# GY_NEO6MV2_Sheet1.net
KiCad netlist of a schematic drawn in Altium Designer
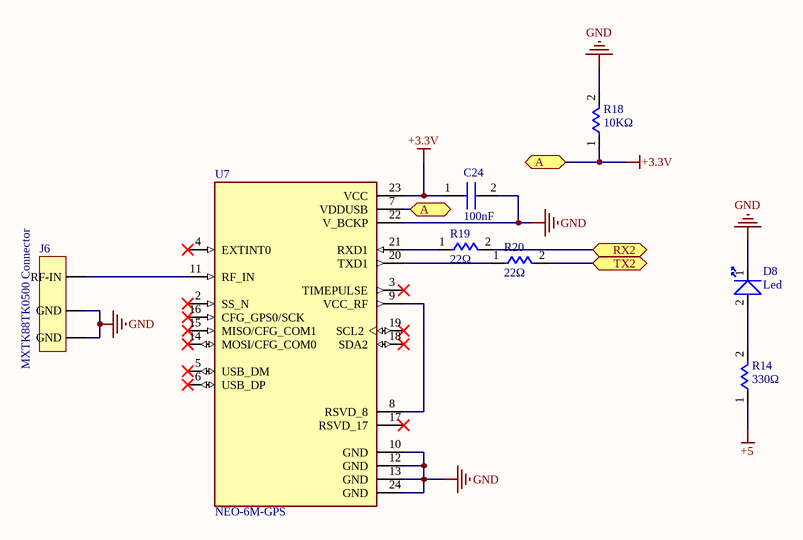
[diagram p0: GY_NEO6MV2_Sheet1.SchDoc]

(export (version "E")
  (design (tool "Eeschema 10.0.6"))
  (components
    (comp (ref "C24")
      (value "100nF")
      (footprint "CAP - 0603")
      (description "Capacitor")
      (libsource (lib "Faydali_Yuk_Schlib1") (part "CAP"))
    )
    (comp (ref "D8")
      (value "Led")
      (footprint "LED - 0603")
      (description "HL-PST-1608U51GC - LED SMD 0603 GREEN 500mcd 120° WATER CLEAR")
      (libsource (lib "Faydali_Yuk_Schlib1") (part "Led"))
    )
    (comp (ref "J6")
      (value "MXTK88TK0500 Connector")
      (footprint "MXTK88TK0500 Connector")
      (description "CABLE ASSEMBLY COAXIAL 0.5m GSC CONN.PL-PL")
      (libsource (lib "Faydali_Yuk_Schlib1") (part "MXTK88TK0500 Connector"))
    )
    (comp (ref "R14")
      (value "330Ω")
      (footprint "RES - 0603")
      (description "SMD Res")
      (libsource (lib "Faydali_Yuk_Schlib1") (part "Res"))
    )
    (comp (ref "R18")
      (value "10KΩ")
      (footprint "RES - 0603")
      (description "SMD Res")
      (libsource (lib "Faydali_Yuk_Schlib1") (part "Res"))
    )
    (comp (ref "R19")
      (value "22Ω")
      (footprint "RES - 0603")
      (description "SMD Res")
      (libsource (lib "Faydali_Yuk_Schlib1") (part "Res"))
    )
    (comp (ref "R20")
      (value "22Ω")
      (footprint "RES - 0603")
      (description "SMD Res")
      (libsource (lib "Faydali_Yuk_Schlib1") (part "Res"))
    )
    (comp (ref "U7")
      (value "NEO-6M-GPS")
      (footprint "XCVR_NEO-6M-GPS")
      (description "SMD GPS Module;")
      (fields (field (name "MF") "u-blox"))
      (libsource (lib "Faydali_Yuk_Schlib1") (part "NEO-6M-GPS"))
    )
  )
  (nets
    (net (code "1") (name "+3.3V") (class "Default")
      (node (ref "C24") (pin "1") (pinfunction "1_1") (pintype "passive"))
      (node (ref "R18") (pin "1") (pinfunction "1_1") (pintype "passive"))
      (node (ref "U7") (pin "23") (pinfunction "VCC_23") (pintype "power_in"))
      (node (ref "U7") (pin "7") (pinfunction "VDDUSB_7") (pintype "power_in"))
    )
    (net (code "2") (name "+5") (class "Default")
      (node (ref "R14") (pin "1") (pinfunction "1_1") (pintype "passive"))
    )
    (net (code "3") (name "/RX2") (class "Default")
      (node (ref "R19") (pin "2") (pinfunction "2_2") (pintype "passive"))
    )
    (net (code "4") (name "/TX2") (class "Default")
      (node (ref "R20") (pin "2") (pinfunction "2_2") (pintype "passive"))
    )
    (net (code "5") (name "GND") (class "Default")
      (node (ref "C24") (pin "2") (pinfunction "2_2") (pintype "passive"))
      (node (ref "D8") (pin "1") (pinfunction "1_1") (pintype "passive"))
      (node (ref "J6") (pin "1") (pinfunction "GND_1") (pintype "passive"))
      (node (ref "J6") (pin "2") (pinfunction "GND_2") (pintype "passive"))
      (node (ref "R18") (pin "2") (pinfunction "2_2") (pintype "passive"))
      (node (ref "U7") (pin "10") (pinfunction "GND_10") (pintype "power_in"))
      (node (ref "U7") (pin "12") (pinfunction "GND_12") (pintype "power_in"))
      (node (ref "U7") (pin "13") (pinfunction "GND_13") (pintype "power_in"))
      (node (ref "U7") (pin "22") (pinfunction "V_BCKP_22") (pintype "power_in"))
      (node (ref "U7") (pin "24") (pinfunction "GND_24") (pintype "power_in"))
    )
    (net (code "6") (name "Net-(D8-Pad2)") (class "Default")
      (node (ref "D8") (pin "2") (pinfunction "2_2") (pintype "passive"))
      (node (ref "R14") (pin "2") (pinfunction "2_2") (pintype "passive"))
    )
    (net (code "7") (name "Net-(J6-RF-IN)") (class "Default")
      (node (ref "J6") (pin "3") (pinfunction "RF-IN_3") (pintype "passive"))
      (node (ref "U7") (pin "11") (pinfunction "RF_IN_11") (pintype "input"))
    )
    (net (code "8") (name "Net-(U7-RSVD_8)") (class "Default")
      (node (ref "U7") (pin "8") (pinfunction "RSVD_8_8") (pintype "passive"))
      (node (ref "U7") (pin "9") (pinfunction "VCC_RF_9") (pintype "output"))
    )
    (net (code "9") (name "Net-(U7-RXD1)") (class "Default")
      (node (ref "R19") (pin "1") (pinfunction "1_1") (pintype "passive"))
      (node (ref "U7") (pin "21") (pinfunction "RXD1_21") (pintype "input"))
    )
    (net (code "10") (name "Net-(U7-TXD1)") (class "Default")
      (node (ref "R20") (pin "1") (pinfunction "1_1") (pintype "passive"))
      (node (ref "U7") (pin "20") (pinfunction "TXD1_20") (pintype "output"))
    )
    (net (code "11") (name "unconnected-(U7-CFG_GPS0{slash}SCK-Pad16)") (class "Default")
      (node (ref "U7") (pin "16") (pinfunction "CFG_GPS0/SCK_16") (pintype "input+no_connect"))
    )
    (net (code "12") (name "unconnected-(U7-EXTINT0-Pad4)") (class "Default")
      (node (ref "U7") (pin "4") (pinfunction "EXTINT0_4") (pintype "input+no_connect"))
    )
    (net (code "13") (name "unconnected-(U7-MISO{slash}CFG_COM1-Pad15)") (class "Default")
      (node (ref "U7") (pin "15") (pinfunction "MISO/CFG_COM1_15") (pintype "input+no_connect"))
    )
    (net (code "14") (name "unconnected-(U7-MOSI{slash}CFG_COM0-Pad14)") (class "Default")
      (node (ref "U7") (pin "14") (pinfunction "MOSI/CFG_COM0_14") (pintype "bidirectional+no_connect"))
    )
    (net (code "15") (name "unconnected-(U7-RSVD_17-Pad17)") (class "Default")
      (node (ref "U7") (pin "17") (pinfunction "RSVD_17_17") (pintype "passive+no_connect"))
    )
    (net (code "16") (name "unconnected-(U7-SCL2-Pad19)") (class "Default")
      (node (ref "U7") (pin "19") (pinfunction "SCL2_19") (pintype "bidirectional+no_connect"))
    )
    (net (code "17") (name "unconnected-(U7-SDA2-Pad18)") (class "Default")
      (node (ref "U7") (pin "18") (pinfunction "SDA2_18") (pintype "bidirectional+no_connect"))
    )
    (net (code "18") (name "unconnected-(U7-SS_N-Pad2)") (class "Default")
      (node (ref "U7") (pin "2") (pinfunction "SS_N_2") (pintype "input+no_connect"))
    )
    (net (code "19") (name "unconnected-(U7-TIMEPULSE-Pad3)") (class "Default")
      (node (ref "U7") (pin "3") (pinfunction "TIMEPULSE_3") (pintype "output+no_connect"))
    )
    (net (code "20") (name "unconnected-(U7-USB_DM-Pad5)") (class "Default")
      (node (ref "U7") (pin "5") (pinfunction "USB_DM_5") (pintype "bidirectional+no_connect"))
    )
    (net (code "21") (name "unconnected-(U7-USB_DP-Pad6)") (class "Default")
      (node (ref "U7") (pin "6") (pinfunction "USB_DP_6") (pintype "bidirectional+no_connect"))
    )
  )
)
